# StripConnectorUSBStrip.net
KiCad netlist of a schematic drawn in EAGLE
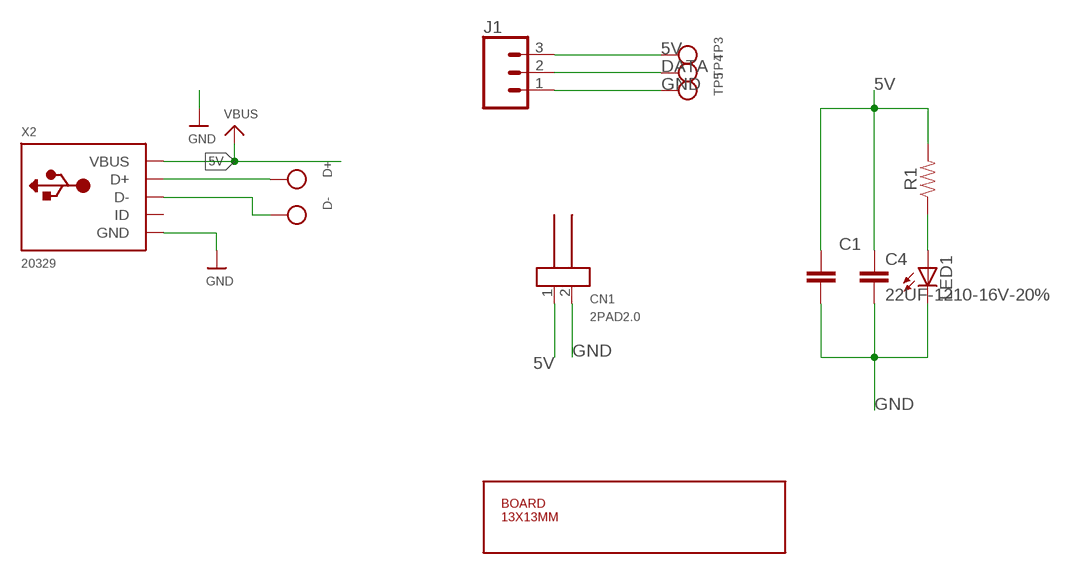
[diagram p0: schematic, sheet 1]

(export (version "E")
  (design (tool "Eeschema 10.0.6"))
  (components
    (comp (ref "C1")
      (value "CAPACITOR_NPOL-0805")
      (footprint "eagle-import:C805")
      (libsource (lib "eagle-import") (part "CAPACITOR_NPOL-0805"))
    )
    (comp (ref "C4")
      (value "22UF-1210-16V-20%")
      (footprint "eagle-import:1210")
      (libsource (lib "eagle-import") (part "22UF-1210-16V-20%"))
    )
    (comp (ref "CN1")
      (value "2PAD2.0")
      (footprint "eagle-import:2POLE_P2.0")
      (libsource (lib "eagle-import") (part "2PAD2.0"))
    )
    (comp (ref "D+")
      (value "TESTPOINTROUND1MM")
      (footprint "eagle-import:TESTPOINT_ROUND_1MM")
      (libsource (lib "eagle-import") (part "TESTPOINTROUND1MM"))
    )
    (comp (ref "D-")
      (value "TESTPOINTROUND1MM")
      (footprint "eagle-import:TESTPOINT_ROUND_1MM")
      (libsource (lib "eagle-import") (part "TESTPOINTROUND1MM"))
    )
    (comp (ref "J1")
      (value "CONN_03LONGPADS")
      (footprint "eagle-import:1X03_LONGPADS")
      (libsource (lib "eagle-import") (part "CONN_03LONGPADS"))
    )
    (comp (ref "LED1")
      (value "LED-0805")
      (footprint "eagle-import:LED-805")
      (libsource (lib "eagle-import") (part "LED-0805"))
    )
    (comp (ref "R1")
      (value "RESISTOR0805")
      (footprint "eagle-import:0805")
      (libsource (lib "eagle-import") (part "RESISTOR0805"))
    )
    (comp (ref "TP3")
      (value "TESTPOINTROUND1MM")
      (footprint "eagle-import:TESTPOINT_ROUND_1MM")
      (libsource (lib "eagle-import") (part "TESTPOINTROUND1MM"))
    )
    (comp (ref "TP4")
      (value "TESTPOINTROUND1MM")
      (footprint "eagle-import:TESTPOINT_ROUND_1MM")
      (libsource (lib "eagle-import") (part "TESTPOINTROUND1MM"))
    )
    (comp (ref "TP5")
      (value "TESTPOINTROUND1MM")
      (footprint "eagle-import:TESTPOINT_ROUND_1MM")
      (libsource (lib "eagle-import") (part "TESTPOINTROUND1MM"))
    )
    (comp (ref "U$1")
      (value "BOARD_13X13MM")
      (footprint "eagle-import:13X13")
      (libsource (lib "eagle-import") (part "BOARD_13X13MM"))
    )
    (comp (ref "X2")
      (value "20329")
      (footprint "eagle-import:4UCONN_20329_V2")
      (libsource (lib "eagle-import") (part "USB_MICRO_20329_V2"))
    )
  )
  (nets
    (net (code "1") (name "/DATA") (class "Default")
      (node (ref "J1") (pin "2") (pinfunction "2_2") (pintype "passive"))
      (node (ref "TP4") (pin "P$1") (pinfunction "P$1_P$1") (pintype "bidirectional"))
    )
    (net (code "2") (name "5V") (class "Default")
      (node (ref "C1") (pin "1") (pinfunction "1_1") (pintype "passive"))
      (node (ref "C4") (pin "1") (pinfunction "1_1") (pintype "passive"))
      (node (ref "CN1") (pin "1") (pinfunction "P$1_1") (pintype "bidirectional"))
      (node (ref "J1") (pin "3") (pinfunction "3_3") (pintype "passive"))
      (node (ref "R1") (pin "2") (pinfunction "2_2") (pintype "passive"))
      (node (ref "TP3") (pin "P$1") (pinfunction "P$1_P$1") (pintype "bidirectional"))
      (node (ref "X2") (pin "VBUS") (pinfunction "VBUS_VBUS") (pintype "power_in"))
    )
    (net (code "3") (name "GND") (class "Default")
      (node (ref "C1") (pin "2") (pinfunction "2_2") (pintype "passive"))
      (node (ref "C4") (pin "2") (pinfunction "2_2") (pintype "passive"))
      (node (ref "CN1") (pin "2") (pinfunction "P$2_2") (pintype "bidirectional"))
      (node (ref "J1") (pin "1") (pinfunction "1_1") (pintype "passive"))
      (node (ref "LED1") (pin "C") (pinfunction "C_C") (pintype "passive"))
      (node (ref "TP5") (pin "P$1") (pinfunction "P$1_P$1") (pintype "bidirectional"))
      (node (ref "X2") (pin "BASE@1") (pinfunction "GND_BASE@1") (pintype "power_in"))
      (node (ref "X2") (pin "BASE@2") (pinfunction "GND_BASE@2") (pintype "power_in"))
      (node (ref "X2") (pin "GND") (pinfunction "GND_GND") (pintype "power_in"))
      (node (ref "X2") (pin "SPRT@1") (pinfunction "GND_SPRT@1") (pintype "power_in"))
      (node (ref "X2") (pin "SPRT@2") (pinfunction "GND_SPRT@2") (pintype "power_in"))
      (node (ref "X2") (pin "SPRT@3") (pinfunction "GND_SPRT@3") (pintype "power_in"))
      (node (ref "X2") (pin "SPRT@4") (pinfunction "GND_SPRT@4") (pintype "power_in"))
    )
    (net (code "4") (name "Net-(D+-PadP$1)") (class "Default")
      (node (ref "D+") (pin "P$1") (pinfunction "P$1_P$1") (pintype "bidirectional"))
      (node (ref "X2") (pin "D+") (pinfunction "D+_D+") (pintype "bidirectional"))
    )
    (net (code "5") (name "Net-(D--PadP$1)") (class "Default")
      (node (ref "D-") (pin "P$1") (pinfunction "P$1_P$1") (pintype "bidirectional"))
      (node (ref "X2") (pin "D-") (pinfunction "D-_D-") (pintype "bidirectional"))
    )
    (net (code "6") (name "Net-(LED1-PadA)") (class "Default")
      (node (ref "LED1") (pin "A") (pinfunction "A_A") (pintype "passive"))
      (node (ref "R1") (pin "1") (pinfunction "1_1") (pintype "passive"))
    )
    (net (code "7") (name "unconnected-(X2-PadID)") (class "Default")
      (node (ref "X2") (pin "ID") (pinfunction "ID_ID") (pintype "bidirectional"))
    )
  )
)
